# SMPS-3V.net
KiCad netlist of a schematic drawn in Altium Designer
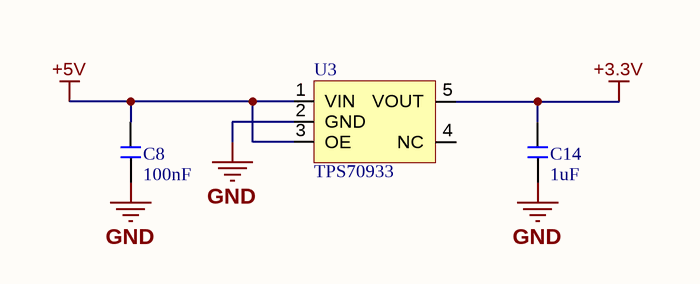
[diagram p0: SMPS-3V.SchDoc]

(export (version "E")
  (design (tool "Eeschema 10.0.6"))
  (components
    (comp (ref "C8")
      (value "100nF")
      (footprint "C0603_N")
      (description "Capacitor MLCC")
      (fields
        (field (name "MANUFACTURER") "Yageo")
        (field (name "MANUFACTURER PART NUMBER") "CC0603KRX7R9BB104")
      )
      (libsource (lib "wes") (part "Capacitor"))
    )
    (comp (ref "C14")
      (value "1uF")
      (footprint "C0603_N")
      (description "Capacitor MLCC")
      (fields
        (field (name "MANUFACTURER") "Yageo")
        (field (name "MANUFACTURER PART NUMBER") "CC0603KRX7R9BB104")
      )
      (libsource (lib "wes") (part "Capacitor"))
    )
    (comp (ref "U3") (value "TPS70933") (footprint "SOT23-5_N") (libsource (lib "wes") (part "XC6222")))
  )
  (nets
    (net (code "1") (name "+3.3V") (class "Default")
      (node (ref "C14") (pin "1") (pintype "passive"))
      (node (ref "U3") (pin "5") (pinfunction "VOUT_5") (pintype "passive"))
    )
    (net (code "2") (name "+5V") (class "Default")
      (node (ref "C8") (pin "1") (pintype "passive"))
      (node (ref "U3") (pin "1") (pinfunction "VIN_1") (pintype "passive"))
      (node (ref "U3") (pin "3") (pinfunction "OE_3") (pintype "passive"))
    )
    (net (code "3") (name "GND") (class "Default")
      (node (ref "C14") (pin "2") (pintype "passive"))
      (node (ref "C8") (pin "2") (pintype "passive"))
      (node (ref "U3") (pin "2") (pinfunction "GND_2") (pintype "passive"))
    )
    (net (code "4") (name "unconnected-(U3-NC-Pad4)") (class "Default")
      (node (ref "U3") (pin "4") (pinfunction "NC_4") (pintype "passive"))
    )
  )
)
